# 3_power.net
KiCad netlist of a schematic drawn in Altium Designer
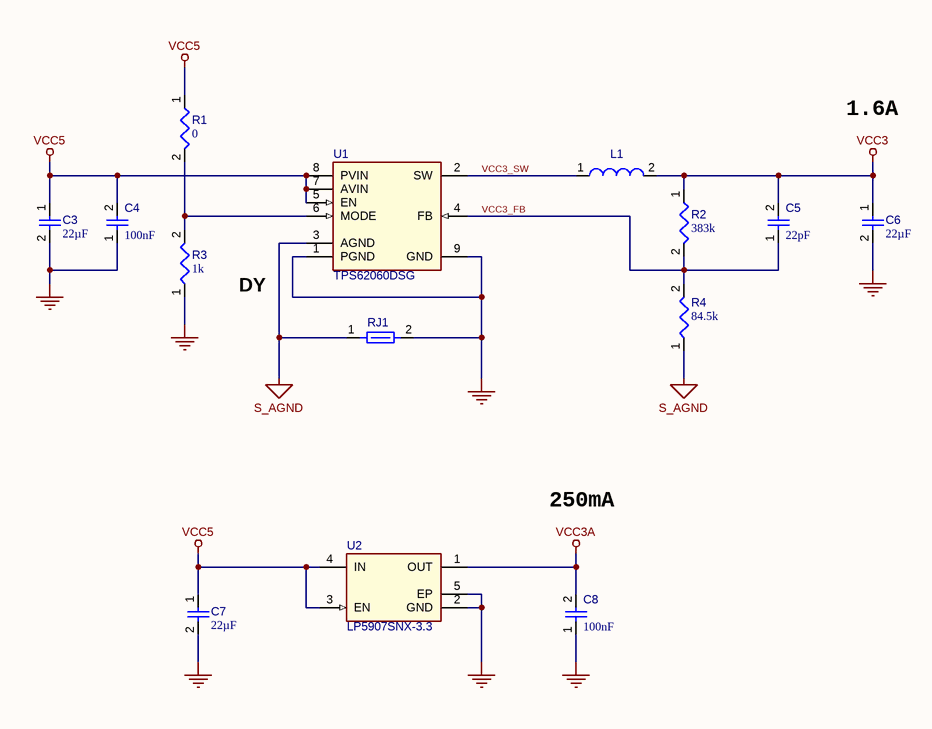
[diagram p0: 3_power.SchDoc]

(export (version "E")
  (design (tool "Eeschema 10.0.6"))
  (components
    (comp (ref "C3")
      (value "22µF")
      (footprint "CAPC0805(2012)145_L")
      (description "Chip Capacitor, 22µF +/-40%, 16V, 0805, Thickness 1.45 mm")
      (fields (field (name "TOLERANCE") "5%") (field (name "Comment") "Capacitor 22µF +/-40% 16V 0805"))
      (libsource (lib "Altium Designer Advanced Course 08") (part "CAP-NP-2"))
    )
    (comp (ref "C4")
      (value "100nF")
      (footprint "CAPC0402(1005)60_L")
      (description "Chip Capacitor, 100nF +/-20%, 10V, 0402, Thickness 0.6 mm")
      (fields (field (name "TOLERANCE") "20%") (field (name "Comment") "Capacitor 100nF +/-20% 10V 0402"))
      (libsource (lib "MHH -  Altium Advanced Course A365 01") (part "CAP-NP-2"))
    )
    (comp (ref "C5")
      (value "22pF")
      (footprint "CAPC0402(1005)60_L")
      (description "Chip Capacitor, 22pF +/-10%, 50V, 0402, Thickness 0.6 mm")
      (fields (field (name "TOLERANCE") "10%") (field (name "Comment") "Capacitor 22pF +/-10% 50V 0402"))
      (libsource (lib "MHH -  Altium Advanced Course A365 01") (part "CAP-NP-2"))
    )
    (comp (ref "C6")
      (value "22µF")
      (footprint "CAPC0805(2012)145_L")
      (description "Chip Capacitor, 22µF +/-40%, 16V, 0805, Thickness 1.45 mm")
      (fields (field (name "TOLERANCE") "5%") (field (name "Comment") "Capacitor 22µF +/-40% 16V 0805"))
      (libsource (lib "Altium Designer Advanced Course 08") (part "CAP-NP-2"))
    )
    (comp (ref "C7")
      (value "22µF")
      (footprint "CAPC0805(2012)145_L")
      (description "Chip Capacitor, 22µF +/-40%, 16V, 0805, Thickness 1.45 mm")
      (fields (field (name "TOLERANCE") "5%") (field (name "Comment") "Capacitor 22µF +/-40% 16V 0805"))
      (libsource (lib "Altium Designer Advanced Course 08") (part "CAP-NP-2"))
    )
    (comp (ref "C8")
      (value "100nF")
      (footprint "CAPC0402(1005)60_L")
      (description "Chip Capacitor, 100nF +/-20%, 10V, 0402, Thickness 0.6 mm")
      (fields (field (name "TOLERANCE") "20%") (field (name "Comment") "Capacitor 100nF +/-20% 10V 0402"))
      (libsource (lib "MHH -  Altium Advanced Course A365 01") (part "CAP-NP-2"))
    )
    (comp (ref "L1")
      (value "VLS252010HBX-2R2M-1")
      (footprint "TDK-VLS252010_V")
      (description "Inductor for Power Circuit, 2.2 uH, +/- 20%, -40 to 105 degC, 2-Pin SMD, RoHS, Tape and Reel")
      (fields (field (name "TOLERANCE") "20%"))
      (libsource (lib "MHH -  Altium Advanced Course A365 01") (part "CMP-001-0020-1"))
    )
    (comp (ref "R1")
      (value "0")
      (footprint "RESC0402(1005)_L")
      (description "Jumper 0402")
      (libsource (lib "MHH -  Altium Advanced Course A365 01") (part "RES-2"))
    )
    (comp (ref "R2")
      (value "383k")
      (footprint "RESC0402(1005)_L")
      (description "Chip Resistor, 383 kOhms, +/-1 %, 63 mW, -55 to 155 degC, 0402")
      (fields (field (name "TOLERANCE") "1%") (field (name "POWER") "63mW"))
      (libsource (lib "MHH -  Altium Advanced Course A365 01") (part "RES-2"))
    )
    (comp (ref "R3")
      (value "1k")
      (footprint "RESC0402(1005)_L")
      (description "Chip Resistor, 1 kOhms, +/-5 %, 63 mW, -55 to 155 degC, 0402")
      (fields (field (name "TOLERANCE") "5%") (field (name "POWER") "63mW"))
      (libsource (lib "MHH -  Altium Advanced Course A365 01") (part "RES-2"))
    )
    (comp (ref "R4")
      (value "84.5k")
      (footprint "RESC0402(1005)_L")
      (description "Chip Resistor, 84,5 kOhms, +/-1 %, 63 mW, -55 to 155 degC, 0402")
      (fields (field (name "TOLERANCE") "1%") (field (name "POWER") "63mW"))
      (libsource (lib "MHH -  Altium Advanced Course A365 01") (part "RES-2"))
    )
    (comp (ref "RJ1")
      (value "Net Tie 10x8mil")
      (footprint "New footprint 1")
      (libsource (lib "MHH -  Altium Advanced Course A365 01") (part "CMP-00022-00002-2"))
    )
    (comp (ref "U1")
      (value "TPS62060DSG")
      (footprint "DSG0008A_V")
      (description "Step Down Converter, 3 MHz, 1.6 A, -45 to 85 degC, 8-Pin WSON, RoHS, Tape and Reel")
      (libsource (lib "MHH -  Altium Advanced Course A365 01") (part "CMP-00002-13_2"))
    )
    (comp (ref "U2")
      (value "LP5907SNX-3.3")
      (footprint "TI-DQN4-480X480TP_V")
      (description "Ultra-Low-Noise, Low-IQ LDO, 3.3 V, 0.25 A, -40 to 125 degC, 4-Pin X2SON, RoHS, Tape and Reel")
      (libsource (lib "Schlib1") (part "CMP-00094-7"))
    )
  )
  (nets
    (net (code "1") (name "/VCC3_FB") (class "Default")
      (node (ref "C5") (pin "1") (pinfunction "1_1") (pintype "passive"))
      (node (ref "R2") (pin "2") (pinfunction "2_2") (pintype "passive"))
      (node (ref "R4") (pin "2") (pinfunction "2_2") (pintype "passive"))
      (node (ref "U1") (pin "4") (pinfunction "FB_4") (pintype "input"))
    )
    (net (code "2") (name "/VCC3_SW") (class "Default")
      (node (ref "L1") (pin "1") (pinfunction "1_1") (pintype "passive"))
      (node (ref "U1") (pin "2") (pinfunction "SW_2") (pintype "power_in"))
    )
    (net (code "3") (name "GND") (class "Default")
      (node (ref "C3") (pin "2") (pinfunction "2_2") (pintype "passive"))
      (node (ref "C4") (pin "1") (pinfunction "1_1") (pintype "passive"))
      (node (ref "C6") (pin "2") (pinfunction "2_2") (pintype "passive"))
      (node (ref "C7") (pin "2") (pinfunction "2_2") (pintype "passive"))
      (node (ref "C8") (pin "1") (pinfunction "1_1") (pintype "passive"))
      (node (ref "R3") (pin "1") (pinfunction "1_1") (pintype "passive"))
      (node (ref "RJ1") (pin "2") (pinfunction "2_2") (pintype "passive"))
      (node (ref "U1") (pin "1") (pinfunction "PGND_1") (pintype "power_in"))
      (node (ref "U1") (pin "9") (pinfunction "GND_9") (pintype "power_in"))
      (node (ref "U2") (pin "2") (pinfunction "GND_2") (pintype "power_in"))
      (node (ref "U2") (pin "5") (pinfunction "EP_5") (pintype "power_in"))
    )
    (net (code "4") (name "Net-(U1-MODE)") (class "Default")
      (node (ref "R1") (pin "2") (pinfunction "2_2") (pintype "passive"))
      (node (ref "R3") (pin "2") (pinfunction "2_2") (pintype "passive"))
      (node (ref "U1") (pin "6") (pinfunction "MODE_6") (pintype "input"))
    )
    (net (code "5") (name "S_AGND") (class "Default")
      (node (ref "R4") (pin "1") (pinfunction "1_1") (pintype "passive"))
      (node (ref "RJ1") (pin "1") (pinfunction "1_1") (pintype "passive"))
      (node (ref "U1") (pin "3") (pinfunction "AGND_3") (pintype "power_in"))
    )
    (net (code "6") (name "VCC3") (class "Default")
      (node (ref "C5") (pin "2") (pinfunction "2_2") (pintype "passive"))
      (node (ref "C6") (pin "1") (pinfunction "1_1") (pintype "passive"))
      (node (ref "L1") (pin "2") (pinfunction "2_2") (pintype "passive"))
      (node (ref "R2") (pin "1") (pinfunction "1_1") (pintype "passive"))
    )
    (net (code "7") (name "VCC3A") (class "Default")
      (node (ref "C8") (pin "2") (pinfunction "2_2") (pintype "passive"))
      (node (ref "U2") (pin "1") (pinfunction "OUT_1") (pintype "power_in"))
    )
    (net (code "8") (name "VCC5") (class "Default")
      (node (ref "C3") (pin "1") (pinfunction "1_1") (pintype "passive"))
      (node (ref "C4") (pin "2") (pinfunction "2_2") (pintype "passive"))
      (node (ref "C7") (pin "1") (pinfunction "1_1") (pintype "passive"))
      (node (ref "R1") (pin "1") (pinfunction "1_1") (pintype "passive"))
      (node (ref "U1") (pin "5") (pinfunction "EN_5") (pintype "input"))
      (node (ref "U1") (pin "7") (pinfunction "AVIN_7") (pintype "power_in"))
      (node (ref "U1") (pin "8") (pinfunction "PVIN_8") (pintype "power_in"))
      (node (ref "U2") (pin "3") (pinfunction "EN_3") (pintype "input"))
      (node (ref "U2") (pin "4") (pinfunction "IN_4") (pintype "power_in"))
    )
  )
)
